# Safety_2019_V_3_0_Faults.net
KiCad netlist of a schematic drawn in Altium Designer
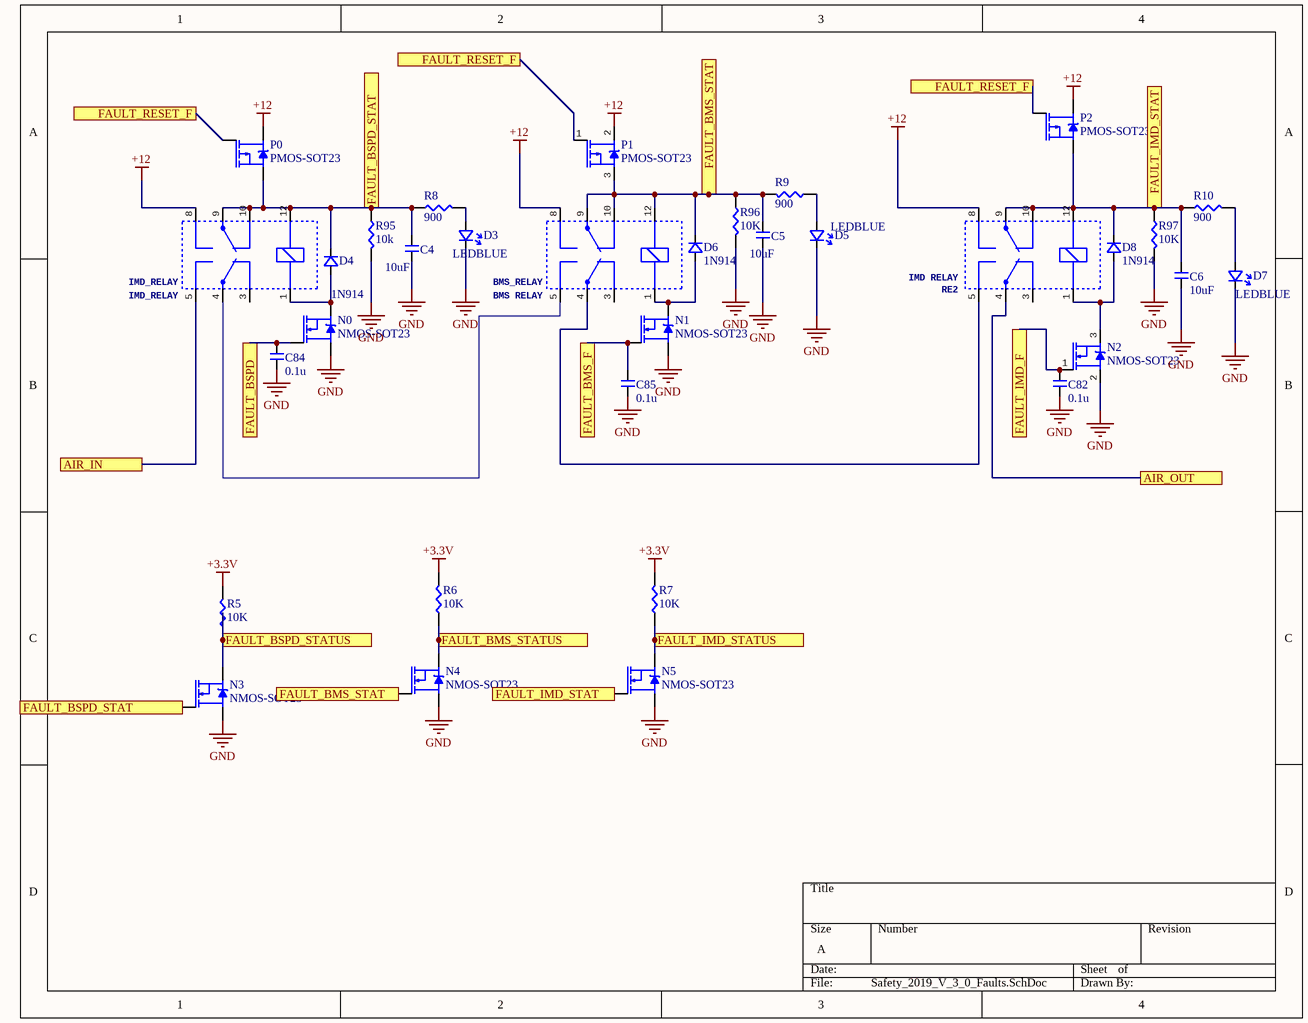
[diagram p0: Safety_2019_V_3_0_Faults.SchDoc]

(export (version "E")
  (design (tool "Eeschema 10.0.6"))
  (components
    (comp (ref "BMS_RELAY")
      (value "BMS RELAY")
      (footprint "RELAY-DPDT_EC2")
      (libsource (lib "ife19_Elec_Library") (part "RELAY_EC2"))
    )
    (comp (ref "C4")
      (value "10uF")
      (footprint "CAP-0603")
      (libsource (lib "ife19_Elec_Library") (part "CAP-0603"))
    )
    (comp (ref "C5")
      (value "10uF")
      (footprint "CAP-0603")
      (libsource (lib "ife19_Elec_Library") (part "CAP-0603"))
    )
    (comp (ref "C6")
      (value "10uF")
      (footprint "CAP-0603")
      (libsource (lib "ife19_Elec_Library") (part "CAP-0603"))
    )
    (comp (ref "C82")
      (value "0.1u")
      (footprint "CAP-0603")
      (libsource (lib "ife19_Elec_Library") (part "CAP-0603"))
    )
    (comp (ref "C84")
      (value "0.1u")
      (footprint "CAP-0603")
      (libsource (lib "ife19_Elec_Library") (part "CAP-0603"))
    )
    (comp (ref "C85")
      (value "0.1u")
      (footprint "CAP-0603")
      (libsource (lib "ife19_Elec_Library") (part "CAP-0603"))
    )
    (comp (ref "D3")
      (value "LEDBLUE")
      (footprint "LEDBLUE-0603")
      (libsource (lib "ife19_Elec_Library") (part "LEDBLUE-0603"))
    )
    (comp (ref "D4")
      (value "1N914")
      (footprint "DO41-10")
      (libsource (lib "ife19_Elec_Library") (part "DIODE-DO41-10"))
    )
    (comp (ref "D5")
      (value "LEDBLUE")
      (footprint "LEDBLUE-0603")
      (libsource (lib "ife19_Elec_Library") (part "LEDBLUE-0603"))
    )
    (comp (ref "D6")
      (value "1N914")
      (footprint "DO41-10")
      (libsource (lib "ife19_Elec_Library") (part "DIODE-DO41-10"))
    )
    (comp (ref "D7")
      (value "LEDBLUE")
      (footprint "LEDBLUE-0603")
      (libsource (lib "ife19_Elec_Library") (part "LEDBLUE-0603"))
    )
    (comp (ref "D8")
      (value "1N914")
      (footprint "DO41-10")
      (libsource (lib "ife19_Elec_Library") (part "DIODE-DO41-10"))
    )
    (comp (ref "IMD_RELAY")
      (value "IMD_RELAY")
      (footprint "RELAY-DPDT_EC2")
      (libsource (lib "ife19_Elec_Library") (part "RELAY_EC2"))
    )
    (comp (ref "N0")
      (value "NMOS-SOT23")
      (footprint "SOT23")
      (libsource (lib "ife19_Elec_Library") (part "NMOS-SOT23"))
    )
    (comp (ref "N1")
      (value "NMOS-SOT23")
      (footprint "SOT23")
      (libsource (lib "ife19_Elec_Library") (part "NMOS-SOT23"))
    )
    (comp (ref "N2") (value "NMOS-SOT23") (footprint "SOT23") (libsource (lib "") (part "NMOS-SOT23_1")))
    (comp (ref "N3")
      (value "NMOS-SOT23")
      (footprint "SOT23")
      (libsource (lib "ife19_Elec_Library") (part "NMOS-SOT23"))
    )
    (comp (ref "N4")
      (value "NMOS-SOT23")
      (footprint "SOT23")
      (libsource (lib "ife19_Elec_Library") (part "NMOS-SOT23"))
    )
    (comp (ref "N5")
      (value "NMOS-SOT23")
      (footprint "SOT23")
      (libsource (lib "ife19_Elec_Library") (part "NMOS-SOT23"))
    )
    (comp (ref "P0") (value "PMOS-SOT23") (footprint "SOT23") (libsource (lib "") (part "PMOS-SOT23_1")))
    (comp (ref "P1")
      (value "PMOS-SOT23")
      (footprint "SOT23")
      (libsource (lib "ife19_Elec_Library") (part "PMOS-SOT23"))
    )
    (comp (ref "P2") (value "PMOS-SOT23") (footprint "SOT23") (libsource (lib "") (part "PMOS-SOT23_1")))
    (comp (ref "R5")
      (value "10K")
      (footprint "RES-0603")
      (libsource (lib "ife19_Elec_Library") (part "RES-0603"))
    )
    (comp (ref "R6")
      (value "10K")
      (footprint "RES-0603")
      (libsource (lib "ife19_Elec_Library") (part "RES-0603"))
    )
    (comp (ref "R7")
      (value "10K")
      (footprint "RES-0603")
      (libsource (lib "ife19_Elec_Library") (part "RES-0603"))
    )
    (comp (ref "R8")
      (value "900")
      (footprint "RES-0603")
      (libsource (lib "ife19_Elec_Library") (part "RES-0603"))
    )
    (comp (ref "R9")
      (value "900")
      (footprint "RES-0603")
      (libsource (lib "ife19_Elec_Library") (part "RES-0603"))
    )
    (comp (ref "R10")
      (value "900")
      (footprint "RES-0603")
      (libsource (lib "ife19_Elec_Library") (part "RES-0603"))
    )
    (comp (ref "R95")
      (value "10k")
      (footprint "RES-0603")
      (libsource (lib "ife19_Elec_Library") (part "RES-0603"))
    )
    (comp (ref "R96")
      (value "10K")
      (footprint "RES-0603")
      (libsource (lib "ife19_Elec_Library") (part "RES-0603"))
    )
    (comp (ref "R97")
      (value "10K")
      (footprint "RES-0603")
      (libsource (lib "ife19_Elec_Library") (part "RES-0603"))
    )
    (comp (ref "RE2")
      (value "IMD RELAY")
      (footprint "RELAY-DPDT_EC2")
      (libsource (lib "ife19_Elec_Library") (part "RELAY_EC2"))
    )
  )
  (nets
    (net (code "1") (name "+3.3V") (class "Default")
      (node (ref "R5") (pin "2") (pinfunction "2_2") (pintype "passive"))
      (node (ref "R6") (pin "2") (pinfunction "2_2") (pintype "passive"))
      (node (ref "R7") (pin "2") (pinfunction "2_2") (pintype "passive"))
    )
    (net (code "2") (name "+12") (class "Default")
      (node (ref "BMS_RELAY") (pin "8") (pintype "passive"))
      (node (ref "IMD_RELAY") (pin "8") (pintype "passive"))
      (node (ref "P0") (pin "2") (pinfunction "S_2") (pintype "passive"))
      (node (ref "P1") (pin "2") (pinfunction "S_2") (pintype "passive"))
      (node (ref "P2") (pin "2") (pinfunction "S_2") (pintype "passive"))
      (node (ref "RE2") (pin "8") (pintype "passive"))
    )
    (net (code "3") (name "/AIR_IN") (class "Default") (node (ref "IMD_RELAY") (pin "5") (pintype "passive")))
    (net (code "4") (name "/AIR_OUT") (class "Default") (node (ref "RE2") (pin "4") (pintype "passive")))
    (net (code "5") (name "/FAULT_BMS_F") (class "Default")
      (node (ref "C85") (pin "2") (pinfunction "2_2") (pintype "passive"))
      (node (ref "N1") (pin "1") (pinfunction "G_1") (pintype "passive"))
    )
    (net (code "6") (name "/FAULT_BMS_STAT") (class "Default")
      (node (ref "BMS_RELAY") (pin "10") (pintype "passive"))
      (node (ref "BMS_RELAY") (pin "12") (pintype "passive"))
      (node (ref "BMS_RELAY") (pin "9") (pintype "passive"))
      (node (ref "C5") (pin "1") (pinfunction "1_1") (pintype "passive"))
      (node (ref "D6") (pin "K") (pinfunction "K_K") (pintype "passive"))
      (node (ref "N4") (pin "1") (pinfunction "G_1") (pintype "passive"))
      (node (ref "P1") (pin "3") (pinfunction "D_3") (pintype "passive"))
      (node (ref "R9") (pin "2") (pinfunction "2_2") (pintype "passive"))
      (node (ref "R96") (pin "1") (pinfunction "1_1") (pintype "passive"))
    )
    (net (code "7") (name "/FAULT_BMS_STATUS") (class "Default")
      (node (ref "N4") (pin "3") (pinfunction "D_3") (pintype "passive"))
      (node (ref "R6") (pin "1") (pinfunction "1_1") (pintype "passive"))
    )
    (net (code "8") (name "/FAULT_BSPD") (class "Default")
      (node (ref "C84") (pin "2") (pinfunction "2_2") (pintype "passive"))
      (node (ref "N0") (pin "1") (pinfunction "G_1") (pintype "passive"))
    )
    (net (code "9") (name "/FAULT_BSPD_STAT") (class "Default")
      (node (ref "C4") (pin "1") (pinfunction "1_1") (pintype "passive"))
      (node (ref "D4") (pin "K") (pinfunction "K_K") (pintype "passive"))
      (node (ref "IMD_RELAY") (pin "10") (pintype "passive"))
      (node (ref "IMD_RELAY") (pin "12") (pintype "passive"))
      (node (ref "IMD_RELAY") (pin "9") (pintype "passive"))
      (node (ref "N3") (pin "1") (pinfunction "G_1") (pintype "passive"))
      (node (ref "P0") (pin "3") (pinfunction "D_3") (pintype "passive"))
      (node (ref "R8") (pin "1") (pinfunction "1_1") (pintype "passive"))
      (node (ref "R95") (pin "1") (pinfunction "1_1") (pintype "passive"))
    )
    (net (code "10") (name "/FAULT_BSPD_STATUS") (class "Default")
      (node (ref "N3") (pin "3") (pinfunction "D_3") (pintype "passive"))
      (node (ref "R5") (pin "1") (pinfunction "1_1") (pintype "passive"))
    )
    (net (code "11") (name "/FAULT_IMD_F") (class "Default")
      (node (ref "C82") (pin "2") (pinfunction "2_2") (pintype "passive"))
      (node (ref "N2") (pin "1") (pinfunction "G_1") (pintype "passive"))
    )
    (net (code "12") (name "/FAULT_IMD_STAT") (class "Default")
      (node (ref "C6") (pin "1") (pinfunction "1_1") (pintype "passive"))
      (node (ref "D8") (pin "K") (pinfunction "K_K") (pintype "passive"))
      (node (ref "N5") (pin "1") (pinfunction "G_1") (pintype "passive"))
      (node (ref "P2") (pin "3") (pinfunction "D_3") (pintype "passive"))
      (node (ref "R10") (pin "1") (pinfunction "1_1") (pintype "passive"))
      (node (ref "R97") (pin "1") (pinfunction "1_1") (pintype "passive"))
      (node (ref "RE2") (pin "10") (pintype "passive"))
      (node (ref "RE2") (pin "12") (pintype "passive"))
      (node (ref "RE2") (pin "9") (pintype "passive"))
    )
    (net (code "13") (name "/FAULT_IMD_STATUS") (class "Default")
      (node (ref "N5") (pin "3") (pinfunction "D_3") (pintype "passive"))
      (node (ref "R7") (pin "1") (pinfunction "1_1") (pintype "passive"))
    )
    (net (code "14") (name "/FAULT_RESET_F") (class "Default")
      (node (ref "P0") (pin "1") (pinfunction "G_1") (pintype "passive"))
      (node (ref "P1") (pin "1") (pinfunction "G_1") (pintype "passive"))
      (node (ref "P2") (pin "1") (pinfunction "G_1") (pintype "passive"))
    )
    (net (code "15") (name "GND") (class "Default")
      (node (ref "C4") (pin "2") (pinfunction "2_2") (pintype "passive"))
      (node (ref "C5") (pin "2") (pinfunction "2_2") (pintype "passive"))
      (node (ref "C6") (pin "2") (pinfunction "2_2") (pintype "passive"))
      (node (ref "C82") (pin "1") (pinfunction "1_1") (pintype "passive"))
      (node (ref "C84") (pin "1") (pinfunction "1_1") (pintype "passive"))
      (node (ref "C85") (pin "1") (pinfunction "1_1") (pintype "passive"))
      (node (ref "D3") (pin "K") (pinfunction "K_K") (pintype "passive"))
      (node (ref "D5") (pin "K") (pinfunction "K_K") (pintype "passive"))
      (node (ref "D7") (pin "K") (pinfunction "K_K") (pintype "passive"))
      (node (ref "N0") (pin "2") (pinfunction "S_2") (pintype "passive"))
      (node (ref "N1") (pin "2") (pinfunction "S_2") (pintype "passive"))
      (node (ref "N2") (pin "2") (pinfunction "S_2") (pintype "passive"))
      (node (ref "N3") (pin "2") (pinfunction "S_2") (pintype "passive"))
      (node (ref "N4") (pin "2") (pinfunction "S_2") (pintype "passive"))
      (node (ref "N5") (pin "2") (pinfunction "S_2") (pintype "passive"))
      (node (ref "R95") (pin "2") (pinfunction "2_2") (pintype "passive"))
      (node (ref "R96") (pin "2") (pinfunction "2_2") (pintype "passive"))
      (node (ref "R97") (pin "2") (pinfunction "2_2") (pintype "passive"))
    )
    (net (code "16") (name "Net-(BMS_RELAY-Pad4)") (class "Default")
      (node (ref "BMS_RELAY") (pin "4") (pintype "passive"))
      (node (ref "RE2") (pin "5") (pintype "passive"))
    )
    (net (code "17") (name "Net-(BMS_RELAY-Pad5)") (class "Default")
      (node (ref "BMS_RELAY") (pin "5") (pintype "passive"))
      (node (ref "IMD_RELAY") (pin "4") (pintype "passive"))
    )
    (net (code "18") (name "Net-(D3-PadA)") (class "Default")
      (node (ref "D3") (pin "A") (pinfunction "A_A") (pintype "passive"))
      (node (ref "R8") (pin "2") (pinfunction "2_2") (pintype "passive"))
    )
    (net (code "19") (name "Net-(D5-PadA)") (class "Default")
      (node (ref "D5") (pin "A") (pinfunction "A_A") (pintype "passive"))
      (node (ref "R9") (pin "1") (pinfunction "1_1") (pintype "passive"))
    )
    (net (code "20") (name "Net-(D7-PadA)") (class "Default")
      (node (ref "D7") (pin "A") (pinfunction "A_A") (pintype "passive"))
      (node (ref "R10") (pin "2") (pinfunction "2_2") (pintype "passive"))
    )
    (net (code "21") (name "Net-(N0-D)") (class "Default")
      (node (ref "D4") (pin "A") (pinfunction "A_A") (pintype "passive"))
      (node (ref "IMD_RELAY") (pin "1") (pintype "passive"))
      (node (ref "N0") (pin "3") (pinfunction "D_3") (pintype "passive"))
    )
    (net (code "22") (name "Net-(N1-D)") (class "Default")
      (node (ref "BMS_RELAY") (pin "1") (pintype "passive"))
      (node (ref "D6") (pin "A") (pinfunction "A_A") (pintype "passive"))
      (node (ref "N1") (pin "3") (pinfunction "D_3") (pintype "passive"))
    )
    (net (code "23") (name "Net-(N2-D)") (class "Default")
      (node (ref "D8") (pin "A") (pinfunction "A_A") (pintype "passive"))
      (node (ref "N2") (pin "3") (pinfunction "D_3") (pintype "passive"))
      (node (ref "RE2") (pin "1") (pintype "passive"))
    )
    (net (code "24") (name "unconnected-(BMS_RELAY-Pad3)") (class "Default")
      (node (ref "BMS_RELAY") (pin "3") (pintype "passive"))
    )
    (net (code "25") (name "unconnected-(IMD_RELAY-Pad3)") (class "Default")
      (node (ref "IMD_RELAY") (pin "3") (pintype "passive"))
    )
    (net (code "26") (name "unconnected-(RE2-Pad3)") (class "Default")
      (node (ref "RE2") (pin "3") (pintype "passive"))
    )
  )
)
